# Power_LDO_1V8.net
KiCad netlist of a schematic drawn in Altium Designer
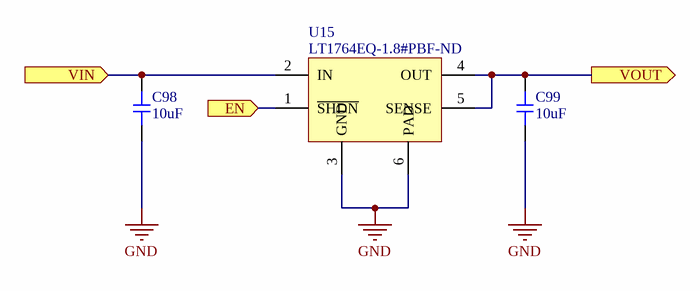
[diagram p0: Power_LDO_1V8.SchDoc]

(export (version "E")
  (design (tool "Eeschema 10.0.6"))
  (components
    (comp (ref "C98")
      (value "10uF")
      (footprint "0603-CAP")
      (description "Capacitor")
      (libsource (lib "AMDC") (part "Capacitor"))
    )
    (comp (ref "C99")
      (value "10uF")
      (footprint "0603-CAP")
      (description "Capacitor")
      (libsource (lib "AMDC") (part "Capacitor"))
    )
    (comp (ref "U15")
      (value "LT1764EQ-1.8#PBF-ND")
      (footprint "5-DDPAK")
      (description "IC REG LINEAR 1.8V 3A 5DDPAK")
      (libsource (lib "AMDC") (part "LT1764EQ-1.8#PBF-ND"))
    )
  )
  (nets
    (net (code "1") (name "/EN") (class "Default")
      (node (ref "U15") (pin "1") (pinfunction "~{SHDN}_1") (pintype "passive"))
    )
    (net (code "2") (name "/VIN") (class "Default")
      (node (ref "C98") (pin "1") (pinfunction "1_1") (pintype "passive"))
      (node (ref "U15") (pin "2") (pinfunction "IN_2") (pintype "passive"))
    )
    (net (code "3") (name "/VOUT") (class "Default")
      (node (ref "C99") (pin "1") (pinfunction "1_1") (pintype "passive"))
      (node (ref "U15") (pin "4") (pinfunction "OUT_4") (pintype "passive"))
      (node (ref "U15") (pin "5") (pinfunction "SENSE_5") (pintype "passive"))
    )
    (net (code "4") (name "GND") (class "Default")
      (node (ref "C98") (pin "2") (pinfunction "2_2") (pintype "passive"))
      (node (ref "C99") (pin "2") (pinfunction "2_2") (pintype "passive"))
      (node (ref "U15") (pin "3") (pinfunction "GND_3") (pintype "passive"))
      (node (ref "U15") (pin "6") (pinfunction "PAD_6") (pintype "passive"))
    )
  )
)
